# Tonemender.net
KiCad netlist of a schematic drawn in EAGLE
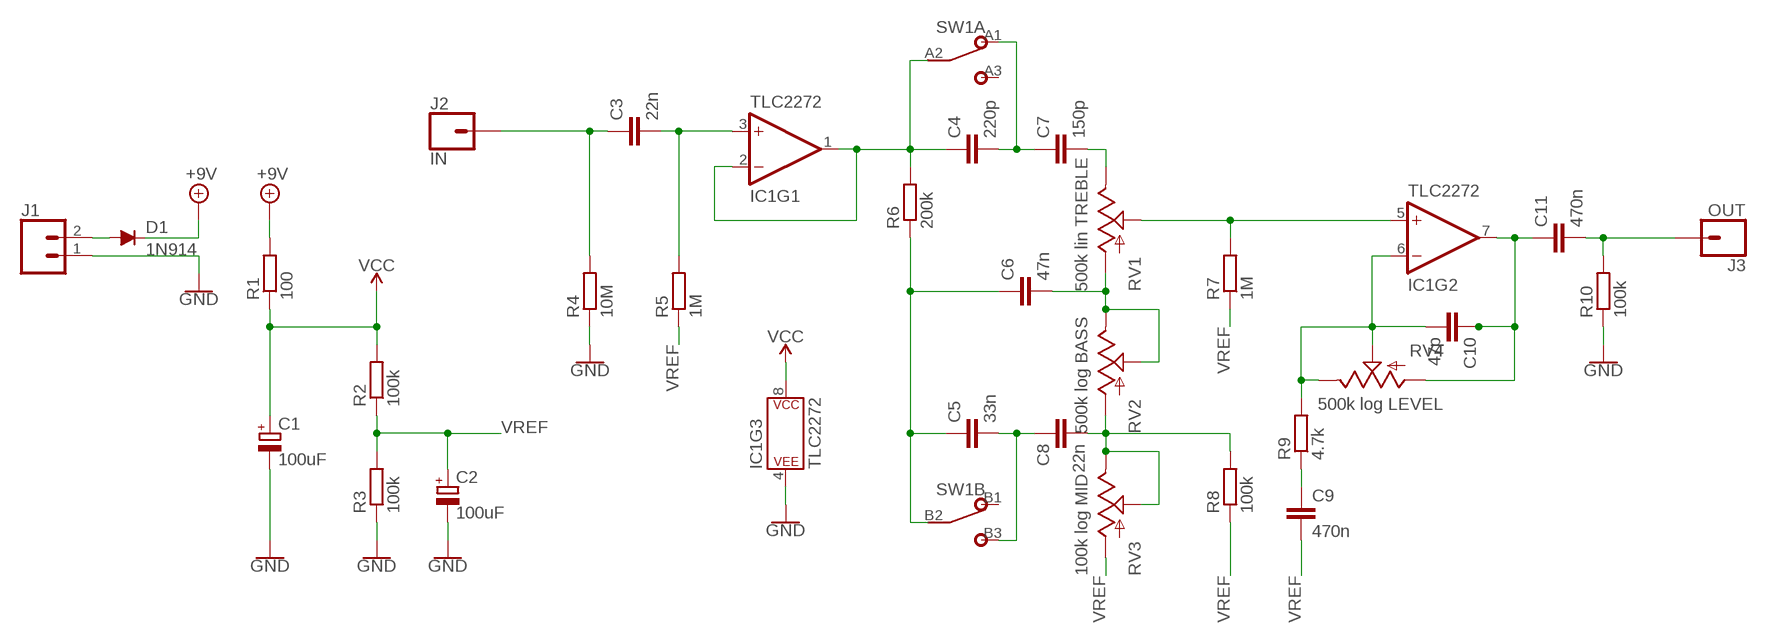
[diagram p0: schematic, sheet 1]

(export (version "E")
  (design (tool "Eeschema 10.0.6"))
  (components
    (comp (ref "C1")
      (value "100uF")
      (footprint "eagle-import:E2,5-5")
      (libsource (lib "eagle-import") (part "CPOL-EUE2.5-5"))
    )
    (comp (ref "C2")
      (value "100uF")
      (footprint "eagle-import:E2,5-5")
      (libsource (lib "eagle-import") (part "CPOL-EUE2.5-5"))
    )
    (comp (ref "C3")
      (value "22n")
      (footprint "eagle-import:C0805")
      (libsource (lib "eagle-import") (part "C-EUC0805"))
    )
    (comp (ref "C4")
      (value "220p")
      (footprint "eagle-import:C0805")
      (libsource (lib "eagle-import") (part "C-EUC0805"))
    )
    (comp (ref "C5")
      (value "33n")
      (footprint "eagle-import:C0805")
      (libsource (lib "eagle-import") (part "C-EUC0805"))
    )
    (comp (ref "C6")
      (value "47n")
      (footprint "eagle-import:C0805")
      (libsource (lib "eagle-import") (part "C-EUC0805"))
    )
    (comp (ref "C7")
      (value "150p")
      (footprint "eagle-import:C0805")
      (libsource (lib "eagle-import") (part "C-EUC0805"))
    )
    (comp (ref "C8")
      (value "22n")
      (footprint "eagle-import:C0805")
      (libsource (lib "eagle-import") (part "C-EUC0805"))
    )
    (comp (ref "C9")
      (value "470n")
      (footprint "eagle-import:C0805")
      (libsource (lib "eagle-import") (part "C-EUC0805"))
    )
    (comp (ref "C10")
      (value "47p")
      (footprint "eagle-import:C0805")
      (libsource (lib "eagle-import") (part "C-EUC0805"))
    )
    (comp (ref "C11")
      (value "470n")
      (footprint "eagle-import:C0805")
      (libsource (lib "eagle-import") (part "C-EUC0805"))
    )
    (comp (ref "D1")
      (value "1N914")
      (footprint "eagle-import:DO35-6")
      (libsource (lib "eagle-import") (part "1N4148-6"))
    )
    (comp (ref "IC1")
      (value "TLC2272")
      (footprint "eagle-import:SO08")
      (libsource (lib "eagle-import") (part "OPAMP-DUALU"))
    )
    (comp (ref "J1")
      (value "CONN_02")
      (footprint "eagle-import:1X02")
      (libsource (lib "eagle-import") (part "CONN_02"))
    )
    (comp (ref "J2")
      (value "IN")
      (footprint "eagle-import:1X01")
      (libsource (lib "eagle-import") (part "CONN_01"))
    )
    (comp (ref "J3")
      (value "OUT")
      (footprint "eagle-import:1X01")
      (libsource (lib "eagle-import") (part "CONN_01"))
    )
    (comp (ref "R1")
      (value "100")
      (footprint "eagle-import:M0805")
      (libsource (lib "eagle-import") (part "R-EU_M0805"))
    )
    (comp (ref "R2")
      (value "100k")
      (footprint "eagle-import:M0805")
      (libsource (lib "eagle-import") (part "R-EU_M0805"))
    )
    (comp (ref "R3")
      (value "100k")
      (footprint "eagle-import:M0805")
      (libsource (lib "eagle-import") (part "R-EU_M0805"))
    )
    (comp (ref "R4")
      (value "10M")
      (footprint "eagle-import:M0805")
      (libsource (lib "eagle-import") (part "R-EU_M0805"))
    )
    (comp (ref "R5")
      (value "1M")
      (footprint "eagle-import:M0805")
      (libsource (lib "eagle-import") (part "R-EU_M0805"))
    )
    (comp (ref "R6")
      (value "200k")
      (footprint "eagle-import:M0805")
      (libsource (lib "eagle-import") (part "R-EU_M0805"))
    )
    (comp (ref "R7")
      (value "1M")
      (footprint "eagle-import:M0805")
      (libsource (lib "eagle-import") (part "R-EU_M0805"))
    )
    (comp (ref "R8")
      (value "100k")
      (footprint "eagle-import:M0805")
      (libsource (lib "eagle-import") (part "R-EU_M0805"))
    )
    (comp (ref "R9")
      (value "4.7k")
      (footprint "eagle-import:M0805")
      (libsource (lib "eagle-import") (part "R-EU_M0805"))
    )
    (comp (ref "R10")
      (value "100k")
      (footprint "eagle-import:M0805")
      (libsource (lib "eagle-import") (part "R-EU_M0805"))
    )
    (comp (ref "RV1")
      (value "500k lin TREBLE")
      (footprint "eagle-import:1X03")
      (libsource (lib "eagle-import") (part "POTPADS"))
    )
    (comp (ref "RV2")
      (value "500k log BASS")
      (footprint "eagle-import:1X03")
      (libsource (lib "eagle-import") (part "POTPADS"))
    )
    (comp (ref "RV3")
      (value "100k log MID")
      (footprint "eagle-import:1X03")
      (libsource (lib "eagle-import") (part "POTPADS"))
    )
    (comp (ref "RV4")
      (value "500k log LEVEL")
      (footprint "eagle-import:1X03")
      (libsource (lib "eagle-import") (part "POTPADS"))
    )
    (comp (ref "SW1")
      (value "DPDTPADS")
      (footprint "eagle-import:DPDT_PADS")
      (libsource (lib "eagle-import") (part "DPDTPADS"))
    )
  )
  (nets
    (net (code "1") (name "+9V") (class "Default")
      (node (ref "D1") (pin "C") (pinfunction "C_C") (pintype "passive"))
      (node (ref "R1") (pin "2") (pinfunction "2_2") (pintype "passive"))
    )
    (net (code "2") (name "/VREF") (class "Default")
      (node (ref "C2") (pin "+") (pinfunction "+_+") (pintype "passive"))
      (node (ref "C9") (pin "2") (pinfunction "2_2") (pintype "passive"))
      (node (ref "R2") (pin "1") (pinfunction "1_1") (pintype "passive"))
      (node (ref "R3") (pin "2") (pinfunction "2_2") (pintype "passive"))
      (node (ref "R5") (pin "1") (pinfunction "1_1") (pintype "passive"))
      (node (ref "R7") (pin "1") (pinfunction "1_1") (pintype "passive"))
      (node (ref "R8") (pin "1") (pinfunction "1_1") (pintype "passive"))
      (node (ref "RV3") (pin "1") (pinfunction "A_1") (pintype "passive"))
    )
    (net (code "3") (name "GND") (class "Default")
      (node (ref "C1") (pin "-") (pinfunction "-_-") (pintype "passive"))
      (node (ref "C2") (pin "-") (pinfunction "-_-") (pintype "passive"))
      (node (ref "IC1") (pin "4") (pinfunction "P$V-_4") (pintype "bidirectional"))
      (node (ref "J1") (pin "1") (pinfunction "1_1") (pintype "passive"))
      (node (ref "R10") (pin "1") (pinfunction "1_1") (pintype "passive"))
      (node (ref "R3") (pin "1") (pinfunction "1_1") (pintype "passive"))
      (node (ref "R4") (pin "1") (pinfunction "1_1") (pintype "passive"))
    )
    (net (code "4") (name "Net-(C3-Pad1)") (class "Default")
      (node (ref "C3") (pin "1") (pinfunction "1_1") (pintype "passive"))
      (node (ref "J2") (pin "1") (pinfunction "1_1") (pintype "passive"))
      (node (ref "R4") (pin "2") (pinfunction "2_2") (pintype "passive"))
    )
    (net (code "5") (name "Net-(C9-Pad1)") (class "Default")
      (node (ref "C9") (pin "1") (pinfunction "1_1") (pintype "passive"))
      (node (ref "R9") (pin "1") (pinfunction "1_1") (pintype "passive"))
    )
    (net (code "6") (name "Net-(C11-Pad2)") (class "Default")
      (node (ref "C11") (pin "2") (pinfunction "2_2") (pintype "passive"))
      (node (ref "J3") (pin "1") (pinfunction "1_1") (pintype "passive"))
      (node (ref "R10") (pin "2") (pinfunction "2_2") (pintype "passive"))
    )
    (net (code "7") (name "Net-(D1-PadA)") (class "Default")
      (node (ref "D1") (pin "A") (pinfunction "A_A") (pintype "passive"))
      (node (ref "J1") (pin "2") (pinfunction "2_2") (pintype "passive"))
    )
    (net (code "8") (name "Net-(IC1A-+IN)") (class "Default")
      (node (ref "C3") (pin "2") (pinfunction "2_2") (pintype "passive"))
      (node (ref "IC1") (pin "3") (pinfunction "+IN_3") (pintype "input"))
      (node (ref "R5") (pin "2") (pinfunction "2_2") (pintype "passive"))
    )
    (net (code "9") (name "Net-(IC1A--IN)") (class "Default")
      (node (ref "C4") (pin "1") (pinfunction "1_1") (pintype "passive"))
      (node (ref "IC1") (pin "1") (pinfunction "OUT_1") (pintype "output"))
      (node (ref "IC1") (pin "2") (pinfunction "-IN_2") (pintype "input"))
      (node (ref "R6") (pin "2") (pinfunction "2_2") (pintype "passive"))
      (node (ref "SW1") (pin "A2") (pinfunction "2_A2") (pintype "passive"))
    )
    (net (code "10") (name "Net-(IC1B-+IN)") (class "Default")
      (node (ref "IC1") (pin "5") (pinfunction "+IN_5") (pintype "input"))
      (node (ref "R7") (pin "2") (pinfunction "2_2") (pintype "passive"))
      (node (ref "RV1") (pin "2") (pinfunction "S_2") (pintype "passive"))
    )
    (net (code "11") (name "Net-(IC1B--IN)") (class "Default")
      (node (ref "C10") (pin "2") (pinfunction "2_2") (pintype "passive"))
      (node (ref "IC1") (pin "6") (pinfunction "-IN_6") (pintype "input"))
      (node (ref "R9") (pin "2") (pinfunction "2_2") (pintype "passive"))
      (node (ref "RV4") (pin "2") (pinfunction "S_2") (pintype "passive"))
      (node (ref "RV4") (pin "3") (pinfunction "E_3") (pintype "passive"))
    )
    (net (code "12") (name "Net-(IC1B-OUT)") (class "Default")
      (node (ref "C10") (pin "1") (pinfunction "1_1") (pintype "passive"))
      (node (ref "C11") (pin "1") (pinfunction "1_1") (pintype "passive"))
      (node (ref "IC1") (pin "7") (pinfunction "OUT_7") (pintype "output"))
      (node (ref "RV4") (pin "1") (pinfunction "A_1") (pintype "passive"))
    )
    (net (code "13") (name "Net-(RV1-A)") (class "Default")
      (node (ref "C6") (pin "2") (pinfunction "2_2") (pintype "passive"))
      (node (ref "RV1") (pin "1") (pinfunction "A_1") (pintype "passive"))
      (node (ref "RV2") (pin "2") (pinfunction "S_2") (pintype "passive"))
      (node (ref "RV2") (pin "3") (pinfunction "E_3") (pintype "passive"))
    )
    (net (code "14") (name "Net-(RV1-E)") (class "Default")
      (node (ref "C7") (pin "2") (pinfunction "2_2") (pintype "passive"))
      (node (ref "RV1") (pin "3") (pinfunction "E_3") (pintype "passive"))
    )
    (net (code "15") (name "Net-(RV2-A)") (class "Default")
      (node (ref "C8") (pin "2") (pinfunction "2_2") (pintype "passive"))
      (node (ref "R8") (pin "2") (pinfunction "2_2") (pintype "passive"))
      (node (ref "RV2") (pin "1") (pinfunction "A_1") (pintype "passive"))
      (node (ref "RV3") (pin "2") (pinfunction "S_2") (pintype "passive"))
      (node (ref "RV3") (pin "3") (pinfunction "E_3") (pintype "passive"))
    )
    (net (code "16") (name "Net-(SW1A-1)") (class "Default")
      (node (ref "C4") (pin "2") (pinfunction "2_2") (pintype "passive"))
      (node (ref "C7") (pin "1") (pinfunction "1_1") (pintype "passive"))
      (node (ref "SW1") (pin "A1") (pinfunction "1_A1") (pintype "passive"))
    )
    (net (code "17") (name "Net-(SW1B-2)") (class "Default")
      (node (ref "C5") (pin "1") (pinfunction "1_1") (pintype "passive"))
      (node (ref "C6") (pin "1") (pinfunction "1_1") (pintype "passive"))
      (node (ref "R6") (pin "1") (pinfunction "1_1") (pintype "passive"))
      (node (ref "SW1") (pin "B2") (pinfunction "2_B2") (pintype "passive"))
    )
    (net (code "18") (name "Net-(SW1B-3)") (class "Default")
      (node (ref "C5") (pin "2") (pinfunction "2_2") (pintype "passive"))
      (node (ref "C8") (pin "1") (pinfunction "1_1") (pintype "passive"))
      (node (ref "SW1") (pin "B3") (pinfunction "3_B3") (pintype "passive"))
    )
    (net (code "19") (name "VCC") (class "Default")
      (node (ref "C1") (pin "+") (pinfunction "+_+") (pintype "passive"))
      (node (ref "IC1") (pin "8") (pinfunction "P$V+_8") (pintype "bidirectional"))
      (node (ref "R1") (pin "1") (pinfunction "1_1") (pintype "passive"))
      (node (ref "R2") (pin "2") (pinfunction "2_2") (pintype "passive"))
    )
    (net (code "20") (name "unconnected-(SW1A-3-PadA3)") (class "Default")
      (node (ref "SW1") (pin "A3") (pinfunction "3_A3") (pintype "passive"))
    )
    (net (code "21") (name "unconnected-(SW1B-1-PadB1)") (class "Default")
      (node (ref "SW1") (pin "B1") (pinfunction "1_B1") (pintype "passive"))
    )
  )
)
